# Led.net
KiCad netlist of a schematic drawn in Altium Designer
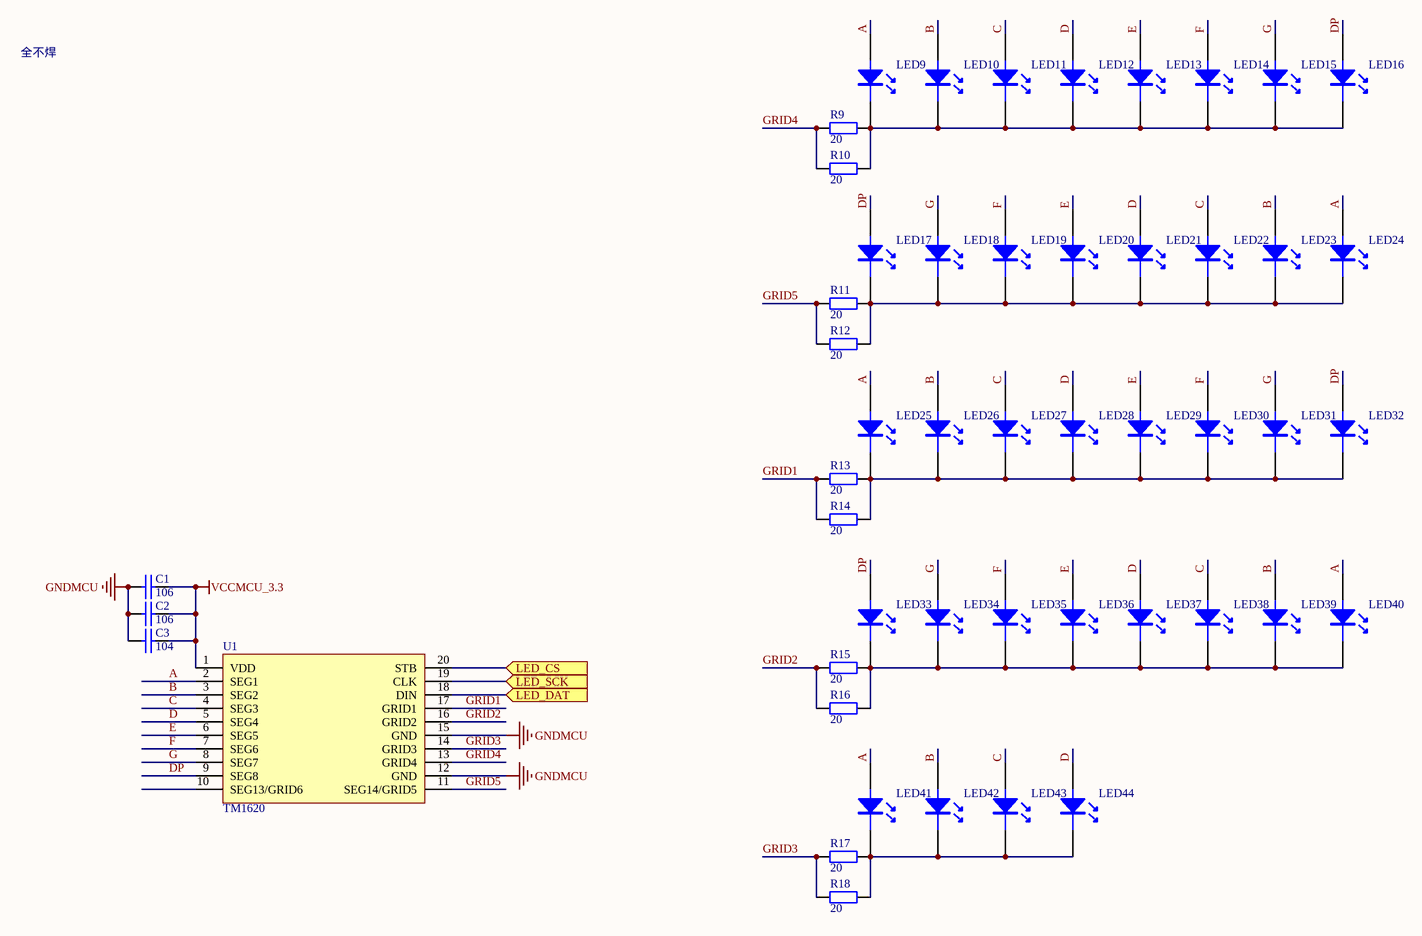
[diagram p0: Led.SchDoc]

(export (version "E")
  (design (tool "Eeschema 10.0.6"))
  (components
    (comp (ref "C1")
      (value "106")
      (footprint "0805/C2")
      (description "Capacitor")
      (libsource (lib "YGInfoSCHLib") (part "CAP"))
    )
    (comp (ref "C2")
      (value "106")
      (footprint "0805/C2")
      (description "Capacitor")
      (libsource (lib "YGInfoSCHLib") (part "CAP"))
    )
    (comp (ref "C3")
      (value "104")
      (footprint "0805/C2")
      (description "Capacitor")
      (libsource (lib "YGInfoSCHLib") (part "CAP"))
    )
    (comp (ref "LED9") (value "~") (footprint "LED0805") (libsource (lib "YGInfoSCHLib") (part "LED-PH")))
    (comp (ref "LED10") (value "~") (footprint "LED0805") (libsource (lib "YGInfoSCHLib") (part "LED-PH")))
    (comp (ref "LED11") (value "~") (footprint "LED0805") (libsource (lib "YGInfoSCHLib") (part "LED-PH")))
    (comp (ref "LED12") (value "~") (footprint "LED0805") (libsource (lib "YGInfoSCHLib") (part "LED-PH")))
    (comp (ref "LED13") (value "~") (footprint "LED0805") (libsource (lib "YGInfoSCHLib") (part "LED-PH")))
    (comp (ref "LED14") (value "~") (footprint "LED0805") (libsource (lib "YGInfoSCHLib") (part "LED-PH")))
    (comp (ref "LED15") (value "~") (footprint "LED0805") (libsource (lib "YGInfoSCHLib") (part "LED-PH")))
    (comp (ref "LED16") (value "~") (footprint "LED0805") (libsource (lib "YGInfoSCHLib") (part "LED-PH")))
    (comp (ref "LED17") (value "~") (footprint "LED0805") (libsource (lib "YGInfoSCHLib") (part "LED-PH")))
    (comp (ref "LED18") (value "~") (footprint "LED0805") (libsource (lib "YGInfoSCHLib") (part "LED-PH")))
    (comp (ref "LED19") (value "~") (footprint "LED0805") (libsource (lib "YGInfoSCHLib") (part "LED-PH")))
    (comp (ref "LED20") (value "~") (footprint "LED0805") (libsource (lib "YGInfoSCHLib") (part "LED-PH")))
    (comp (ref "LED21") (value "~") (footprint "LED0805") (libsource (lib "YGInfoSCHLib") (part "LED-PH")))
    (comp (ref "LED22") (value "~") (footprint "LED0805") (libsource (lib "YGInfoSCHLib") (part "LED-PH")))
    (comp (ref "LED23") (value "~") (footprint "LED0805") (libsource (lib "YGInfoSCHLib") (part "LED-PH")))
    (comp (ref "LED24") (value "~") (footprint "LED0805") (libsource (lib "YGInfoSCHLib") (part "LED-PH")))
    (comp (ref "LED25") (value "~") (footprint "LED0805") (libsource (lib "YGInfoSCHLib") (part "LED-PH")))
    (comp (ref "LED26") (value "~") (footprint "LED0805") (libsource (lib "YGInfoSCHLib") (part "LED-PH")))
    (comp (ref "LED27") (value "~") (footprint "LED0805") (libsource (lib "YGInfoSCHLib") (part "LED-PH")))
    (comp (ref "LED28") (value "~") (footprint "LED0805") (libsource (lib "YGInfoSCHLib") (part "LED-PH")))
    (comp (ref "LED29") (value "~") (footprint "LED0805") (libsource (lib "YGInfoSCHLib") (part "LED-PH")))
    (comp (ref "LED30") (value "~") (footprint "LED0805") (libsource (lib "YGInfoSCHLib") (part "LED-PH")))
    (comp (ref "LED31") (value "~") (footprint "LED0805") (libsource (lib "YGInfoSCHLib") (part "LED-PH")))
    (comp (ref "LED32") (value "~") (footprint "LED0805") (libsource (lib "YGInfoSCHLib") (part "LED-PH")))
    (comp (ref "LED33") (value "~") (footprint "LED0805") (libsource (lib "YGInfoSCHLib") (part "LED-PH")))
    (comp (ref "LED34") (value "~") (footprint "LED0805") (libsource (lib "YGInfoSCHLib") (part "LED-PH")))
    (comp (ref "LED35") (value "~") (footprint "LED0805") (libsource (lib "YGInfoSCHLib") (part "LED-PH")))
    (comp (ref "LED36") (value "~") (footprint "LED0805") (libsource (lib "YGInfoSCHLib") (part "LED-PH")))
    (comp (ref "LED37") (value "~") (footprint "LED0805") (libsource (lib "YGInfoSCHLib") (part "LED-PH")))
    (comp (ref "LED38") (value "~") (footprint "LED0805") (libsource (lib "YGInfoSCHLib") (part "LED-PH")))
    (comp (ref "LED39") (value "~") (footprint "LED0805") (libsource (lib "YGInfoSCHLib") (part "LED-PH")))
    (comp (ref "LED40") (value "~") (footprint "LED0805") (libsource (lib "YGInfoSCHLib") (part "LED-PH")))
    (comp (ref "LED41") (value "~") (footprint "LED0805") (libsource (lib "YGInfoSCHLib") (part "LED-PH")))
    (comp (ref "LED42") (value "~") (footprint "LED0805") (libsource (lib "YGInfoSCHLib") (part "LED-PH")))
    (comp (ref "LED43") (value "~") (footprint "LED0805") (libsource (lib "YGInfoSCHLib") (part "LED-PH")))
    (comp (ref "LED44") (value "~") (footprint "LED0805") (libsource (lib "YGInfoSCHLib") (part "LED-PH")))
    (comp (ref "R9") (value "20") (footprint "0805/R2") (libsource (lib "YGInfoSCHLib") (part "RES1")))
    (comp (ref "R10") (value "20") (footprint "0805/R2") (libsource (lib "YGInfoSCHLib") (part "RES1")))
    (comp (ref "R11") (value "20") (footprint "0805/R2") (libsource (lib "YGInfoSCHLib") (part "RES1")))
    (comp (ref "R12") (value "20") (footprint "0805/R2") (libsource (lib "YGInfoSCHLib") (part "RES1")))
    (comp (ref "R13") (value "20") (footprint "0805/R2") (libsource (lib "YGInfoSCHLib") (part "RES1")))
    (comp (ref "R14") (value "20") (footprint "0805/R2") (libsource (lib "YGInfoSCHLib") (part "RES1")))
    (comp (ref "R15") (value "20") (footprint "0805/R2") (libsource (lib "YGInfoSCHLib") (part "RES1")))
    (comp (ref "R16") (value "20") (footprint "0805/R2") (libsource (lib "YGInfoSCHLib") (part "RES1")))
    (comp (ref "R17") (value "20") (footprint "0805/R2") (libsource (lib "YGInfoSCHLib") (part "RES1")))
    (comp (ref "R18") (value "20") (footprint "0805/R2") (libsource (lib "YGInfoSCHLib") (part "RES1")))
    (comp (ref "U1")
      (value "TM1620")
      (footprint "SOL-20")
      (description "8 段×6 位～10段×4位 串行接口 共阴")
      (libsource (lib "YGInfoSCHLib") (part "TM1620"))
    )
  )
  (nets
    (net (code "1") (name "/A") (class "Default")
      (node (ref "LED24") (pin "1") (pinfunction "1_1") (pintype "passive"))
      (node (ref "LED25") (pin "1") (pinfunction "1_1") (pintype "passive"))
      (node (ref "LED40") (pin "1") (pinfunction "1_1") (pintype "passive"))
      (node (ref "LED41") (pin "1") (pinfunction "1_1") (pintype "passive"))
      (node (ref "LED9") (pin "1") (pinfunction "1_1") (pintype "passive"))
      (node (ref "U1") (pin "2") (pinfunction "SEG1_2") (pintype "passive"))
    )
    (net (code "2") (name "/B") (class "Default")
      (node (ref "LED10") (pin "1") (pinfunction "1_1") (pintype "passive"))
      (node (ref "LED23") (pin "1") (pinfunction "1_1") (pintype "passive"))
      (node (ref "LED26") (pin "1") (pinfunction "1_1") (pintype "passive"))
      (node (ref "LED39") (pin "1") (pinfunction "1_1") (pintype "passive"))
      (node (ref "LED42") (pin "1") (pinfunction "1_1") (pintype "passive"))
      (node (ref "U1") (pin "3") (pinfunction "SEG2_3") (pintype "passive"))
    )
    (net (code "3") (name "/C") (class "Default")
      (node (ref "LED11") (pin "1") (pinfunction "1_1") (pintype "passive"))
      (node (ref "LED22") (pin "1") (pinfunction "1_1") (pintype "passive"))
      (node (ref "LED27") (pin "1") (pinfunction "1_1") (pintype "passive"))
      (node (ref "LED38") (pin "1") (pinfunction "1_1") (pintype "passive"))
      (node (ref "LED43") (pin "1") (pinfunction "1_1") (pintype "passive"))
      (node (ref "U1") (pin "4") (pinfunction "SEG3_4") (pintype "passive"))
    )
    (net (code "4") (name "/D") (class "Default")
      (node (ref "LED12") (pin "1") (pinfunction "1_1") (pintype "passive"))
      (node (ref "LED21") (pin "1") (pinfunction "1_1") (pintype "passive"))
      (node (ref "LED28") (pin "1") (pinfunction "1_1") (pintype "passive"))
      (node (ref "LED37") (pin "1") (pinfunction "1_1") (pintype "passive"))
      (node (ref "LED44") (pin "1") (pinfunction "1_1") (pintype "passive"))
      (node (ref "U1") (pin "5") (pinfunction "SEG4_5") (pintype "passive"))
    )
    (net (code "5") (name "/DP") (class "Default")
      (node (ref "LED16") (pin "1") (pinfunction "1_1") (pintype "passive"))
      (node (ref "LED17") (pin "1") (pinfunction "1_1") (pintype "passive"))
      (node (ref "LED32") (pin "1") (pinfunction "1_1") (pintype "passive"))
      (node (ref "LED33") (pin "1") (pinfunction "1_1") (pintype "passive"))
      (node (ref "U1") (pin "9") (pinfunction "SEG8_9") (pintype "passive"))
    )
    (net (code "6") (name "/E") (class "Default")
      (node (ref "LED13") (pin "1") (pinfunction "1_1") (pintype "passive"))
      (node (ref "LED20") (pin "1") (pinfunction "1_1") (pintype "passive"))
      (node (ref "LED29") (pin "1") (pinfunction "1_1") (pintype "passive"))
      (node (ref "LED36") (pin "1") (pinfunction "1_1") (pintype "passive"))
      (node (ref "U1") (pin "6") (pinfunction "SEG5_6") (pintype "passive"))
    )
    (net (code "7") (name "/F") (class "Default")
      (node (ref "LED14") (pin "1") (pinfunction "1_1") (pintype "passive"))
      (node (ref "LED19") (pin "1") (pinfunction "1_1") (pintype "passive"))
      (node (ref "LED30") (pin "1") (pinfunction "1_1") (pintype "passive"))
      (node (ref "LED35") (pin "1") (pinfunction "1_1") (pintype "passive"))
      (node (ref "U1") (pin "7") (pinfunction "SEG6_7") (pintype "passive"))
    )
    (net (code "8") (name "/G") (class "Default")
      (node (ref "LED15") (pin "1") (pinfunction "1_1") (pintype "passive"))
      (node (ref "LED18") (pin "1") (pinfunction "1_1") (pintype "passive"))
      (node (ref "LED31") (pin "1") (pinfunction "1_1") (pintype "passive"))
      (node (ref "LED34") (pin "1") (pinfunction "1_1") (pintype "passive"))
      (node (ref "U1") (pin "8") (pinfunction "SEG7_8") (pintype "passive"))
    )
    (net (code "9") (name "/GRID1") (class "Default")
      (node (ref "R13") (pin "1") (pinfunction "1_1") (pintype "passive"))
      (node (ref "R14") (pin "1") (pinfunction "1_1") (pintype "passive"))
      (node (ref "U1") (pin "17") (pinfunction "GRID1_17") (pintype "passive"))
    )
    (net (code "10") (name "/GRID2") (class "Default")
      (node (ref "R15") (pin "1") (pinfunction "1_1") (pintype "passive"))
      (node (ref "R16") (pin "1") (pinfunction "1_1") (pintype "passive"))
      (node (ref "U1") (pin "16") (pinfunction "GRID2_16") (pintype "passive"))
    )
    (net (code "11") (name "/GRID3") (class "Default")
      (node (ref "R17") (pin "1") (pinfunction "1_1") (pintype "passive"))
      (node (ref "R18") (pin "1") (pinfunction "1_1") (pintype "passive"))
      (node (ref "U1") (pin "14") (pinfunction "GRID3_14") (pintype "passive"))
    )
    (net (code "12") (name "/GRID4") (class "Default")
      (node (ref "R10") (pin "1") (pinfunction "1_1") (pintype "passive"))
      (node (ref "R9") (pin "1") (pinfunction "1_1") (pintype "passive"))
      (node (ref "U1") (pin "13") (pinfunction "GRID4_13") (pintype "passive"))
    )
    (net (code "13") (name "/GRID5") (class "Default")
      (node (ref "R11") (pin "1") (pinfunction "1_1") (pintype "passive"))
      (node (ref "R12") (pin "1") (pinfunction "1_1") (pintype "passive"))
      (node (ref "U1") (pin "11") (pinfunction "SEG14/GRID5_11") (pintype "passive"))
    )
    (net (code "14") (name "/LED_CS") (class "Default")
      (node (ref "U1") (pin "20") (pinfunction "STB_20") (pintype "passive"))
    )
    (net (code "15") (name "/LED_DAT") (class "Default")
      (node (ref "U1") (pin "18") (pinfunction "DIN_18") (pintype "passive"))
    )
    (net (code "16") (name "/LED_SCK") (class "Default")
      (node (ref "U1") (pin "19") (pinfunction "CLK_19") (pintype "passive"))
    )
    (net (code "17") (name "GNDMCU") (class "Default")
      (node (ref "C1") (pin "2") (pinfunction "2_2") (pintype "passive"))
      (node (ref "C2") (pin "2") (pinfunction "2_2") (pintype "passive"))
      (node (ref "C3") (pin "1") (pinfunction "1_1") (pintype "passive"))
      (node (ref "U1") (pin "12") (pinfunction "GND_12") (pintype "passive"))
      (node (ref "U1") (pin "15") (pinfunction "GND_15") (pintype "passive"))
    )
    (net (code "18") (name "Net-(LED10-Pad2)") (class "Default")
      (node (ref "LED10") (pin "2") (pinfunction "2_2") (pintype "passive"))
      (node (ref "LED11") (pin "2") (pinfunction "2_2") (pintype "passive"))
      (node (ref "LED12") (pin "2") (pinfunction "2_2") (pintype "passive"))
      (node (ref "LED13") (pin "2") (pinfunction "2_2") (pintype "passive"))
      (node (ref "LED14") (pin "2") (pinfunction "2_2") (pintype "passive"))
      (node (ref "LED15") (pin "2") (pinfunction "2_2") (pintype "passive"))
      (node (ref "LED16") (pin "2") (pinfunction "2_2") (pintype "passive"))
      (node (ref "LED9") (pin "2") (pinfunction "2_2") (pintype "passive"))
      (node (ref "R10") (pin "2") (pinfunction "2_2") (pintype "passive"))
      (node (ref "R9") (pin "2") (pinfunction "2_2") (pintype "passive"))
    )
    (net (code "19") (name "Net-(LED17-Pad2)") (class "Default")
      (node (ref "LED17") (pin "2") (pinfunction "2_2") (pintype "passive"))
      (node (ref "LED18") (pin "2") (pinfunction "2_2") (pintype "passive"))
      (node (ref "LED19") (pin "2") (pinfunction "2_2") (pintype "passive"))
      (node (ref "LED20") (pin "2") (pinfunction "2_2") (pintype "passive"))
      (node (ref "LED21") (pin "2") (pinfunction "2_2") (pintype "passive"))
      (node (ref "LED22") (pin "2") (pinfunction "2_2") (pintype "passive"))
      (node (ref "LED23") (pin "2") (pinfunction "2_2") (pintype "passive"))
      (node (ref "LED24") (pin "2") (pinfunction "2_2") (pintype "passive"))
      (node (ref "R11") (pin "2") (pinfunction "2_2") (pintype "passive"))
      (node (ref "R12") (pin "2") (pinfunction "2_2") (pintype "passive"))
    )
    (net (code "20") (name "Net-(LED25-Pad2)") (class "Default")
      (node (ref "LED25") (pin "2") (pinfunction "2_2") (pintype "passive"))
      (node (ref "LED26") (pin "2") (pinfunction "2_2") (pintype "passive"))
      (node (ref "LED27") (pin "2") (pinfunction "2_2") (pintype "passive"))
      (node (ref "LED28") (pin "2") (pinfunction "2_2") (pintype "passive"))
      (node (ref "LED29") (pin "2") (pinfunction "2_2") (pintype "passive"))
      (node (ref "LED30") (pin "2") (pinfunction "2_2") (pintype "passive"))
      (node (ref "LED31") (pin "2") (pinfunction "2_2") (pintype "passive"))
      (node (ref "LED32") (pin "2") (pinfunction "2_2") (pintype "passive"))
      (node (ref "R13") (pin "2") (pinfunction "2_2") (pintype "passive"))
      (node (ref "R14") (pin "2") (pinfunction "2_2") (pintype "passive"))
    )
    (net (code "21") (name "Net-(LED33-Pad2)") (class "Default")
      (node (ref "LED33") (pin "2") (pinfunction "2_2") (pintype "passive"))
      (node (ref "LED34") (pin "2") (pinfunction "2_2") (pintype "passive"))
      (node (ref "LED35") (pin "2") (pinfunction "2_2") (pintype "passive"))
      (node (ref "LED36") (pin "2") (pinfunction "2_2") (pintype "passive"))
      (node (ref "LED37") (pin "2") (pinfunction "2_2") (pintype "passive"))
      (node (ref "LED38") (pin "2") (pinfunction "2_2") (pintype "passive"))
      (node (ref "LED39") (pin "2") (pinfunction "2_2") (pintype "passive"))
      (node (ref "LED40") (pin "2") (pinfunction "2_2") (pintype "passive"))
      (node (ref "R15") (pin "2") (pinfunction "2_2") (pintype "passive"))
      (node (ref "R16") (pin "2") (pinfunction "2_2") (pintype "passive"))
    )
    (net (code "22") (name "Net-(LED41-Pad2)") (class "Default")
      (node (ref "LED41") (pin "2") (pinfunction "2_2") (pintype "passive"))
      (node (ref "LED42") (pin "2") (pinfunction "2_2") (pintype "passive"))
      (node (ref "LED43") (pin "2") (pinfunction "2_2") (pintype "passive"))
      (node (ref "LED44") (pin "2") (pinfunction "2_2") (pintype "passive"))
      (node (ref "R17") (pin "2") (pinfunction "2_2") (pintype "passive"))
      (node (ref "R18") (pin "2") (pinfunction "2_2") (pintype "passive"))
    )
    (net (code "23") (name "VCCMCU_3.3") (class "Default")
      (node (ref "C1") (pin "1") (pinfunction "1_1") (pintype "passive"))
      (node (ref "C2") (pin "1") (pinfunction "1_1") (pintype "passive"))
      (node (ref "C3") (pin "2") (pinfunction "2_2") (pintype "passive"))
      (node (ref "U1") (pin "1") (pinfunction "VDD_1") (pintype "passive"))
    )
    (net (code "24") (name "unconnected-(U1-SEG13{slash}GRID6-Pad10)") (class "Default")
      (node (ref "U1") (pin "10") (pinfunction "SEG13/GRID6_10") (pintype "passive"))
    )
  )
)
